# Talon_I2C.net
KiCad netlist of a schematic drawn in EAGLE
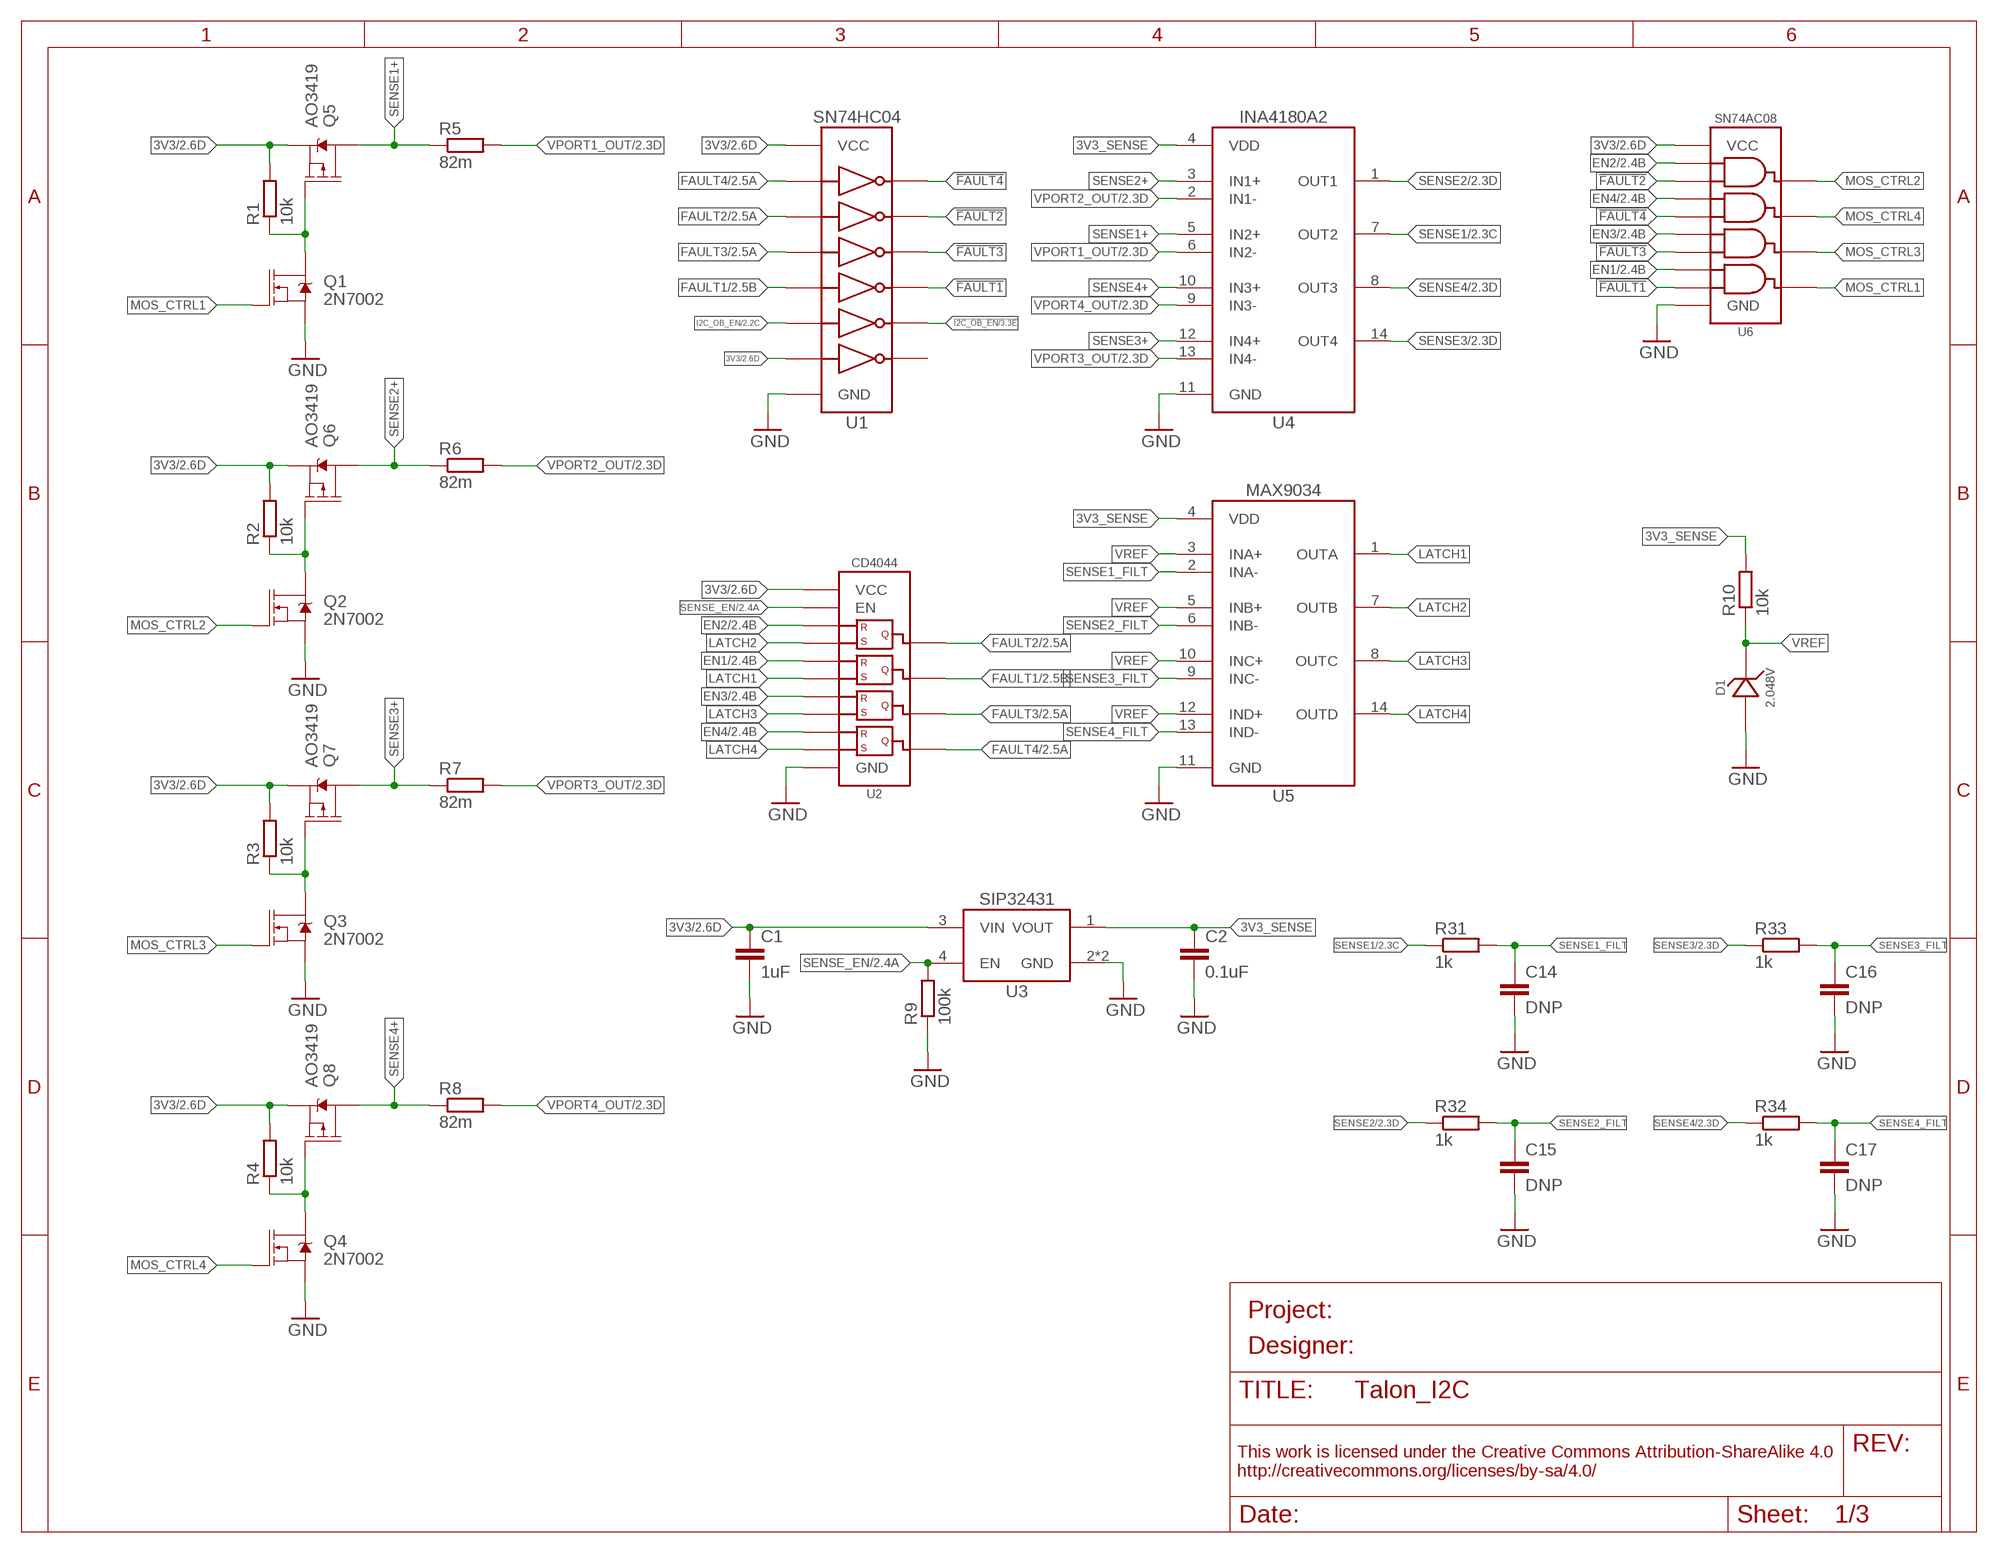
[diagram p0: schematic, sheet 1]
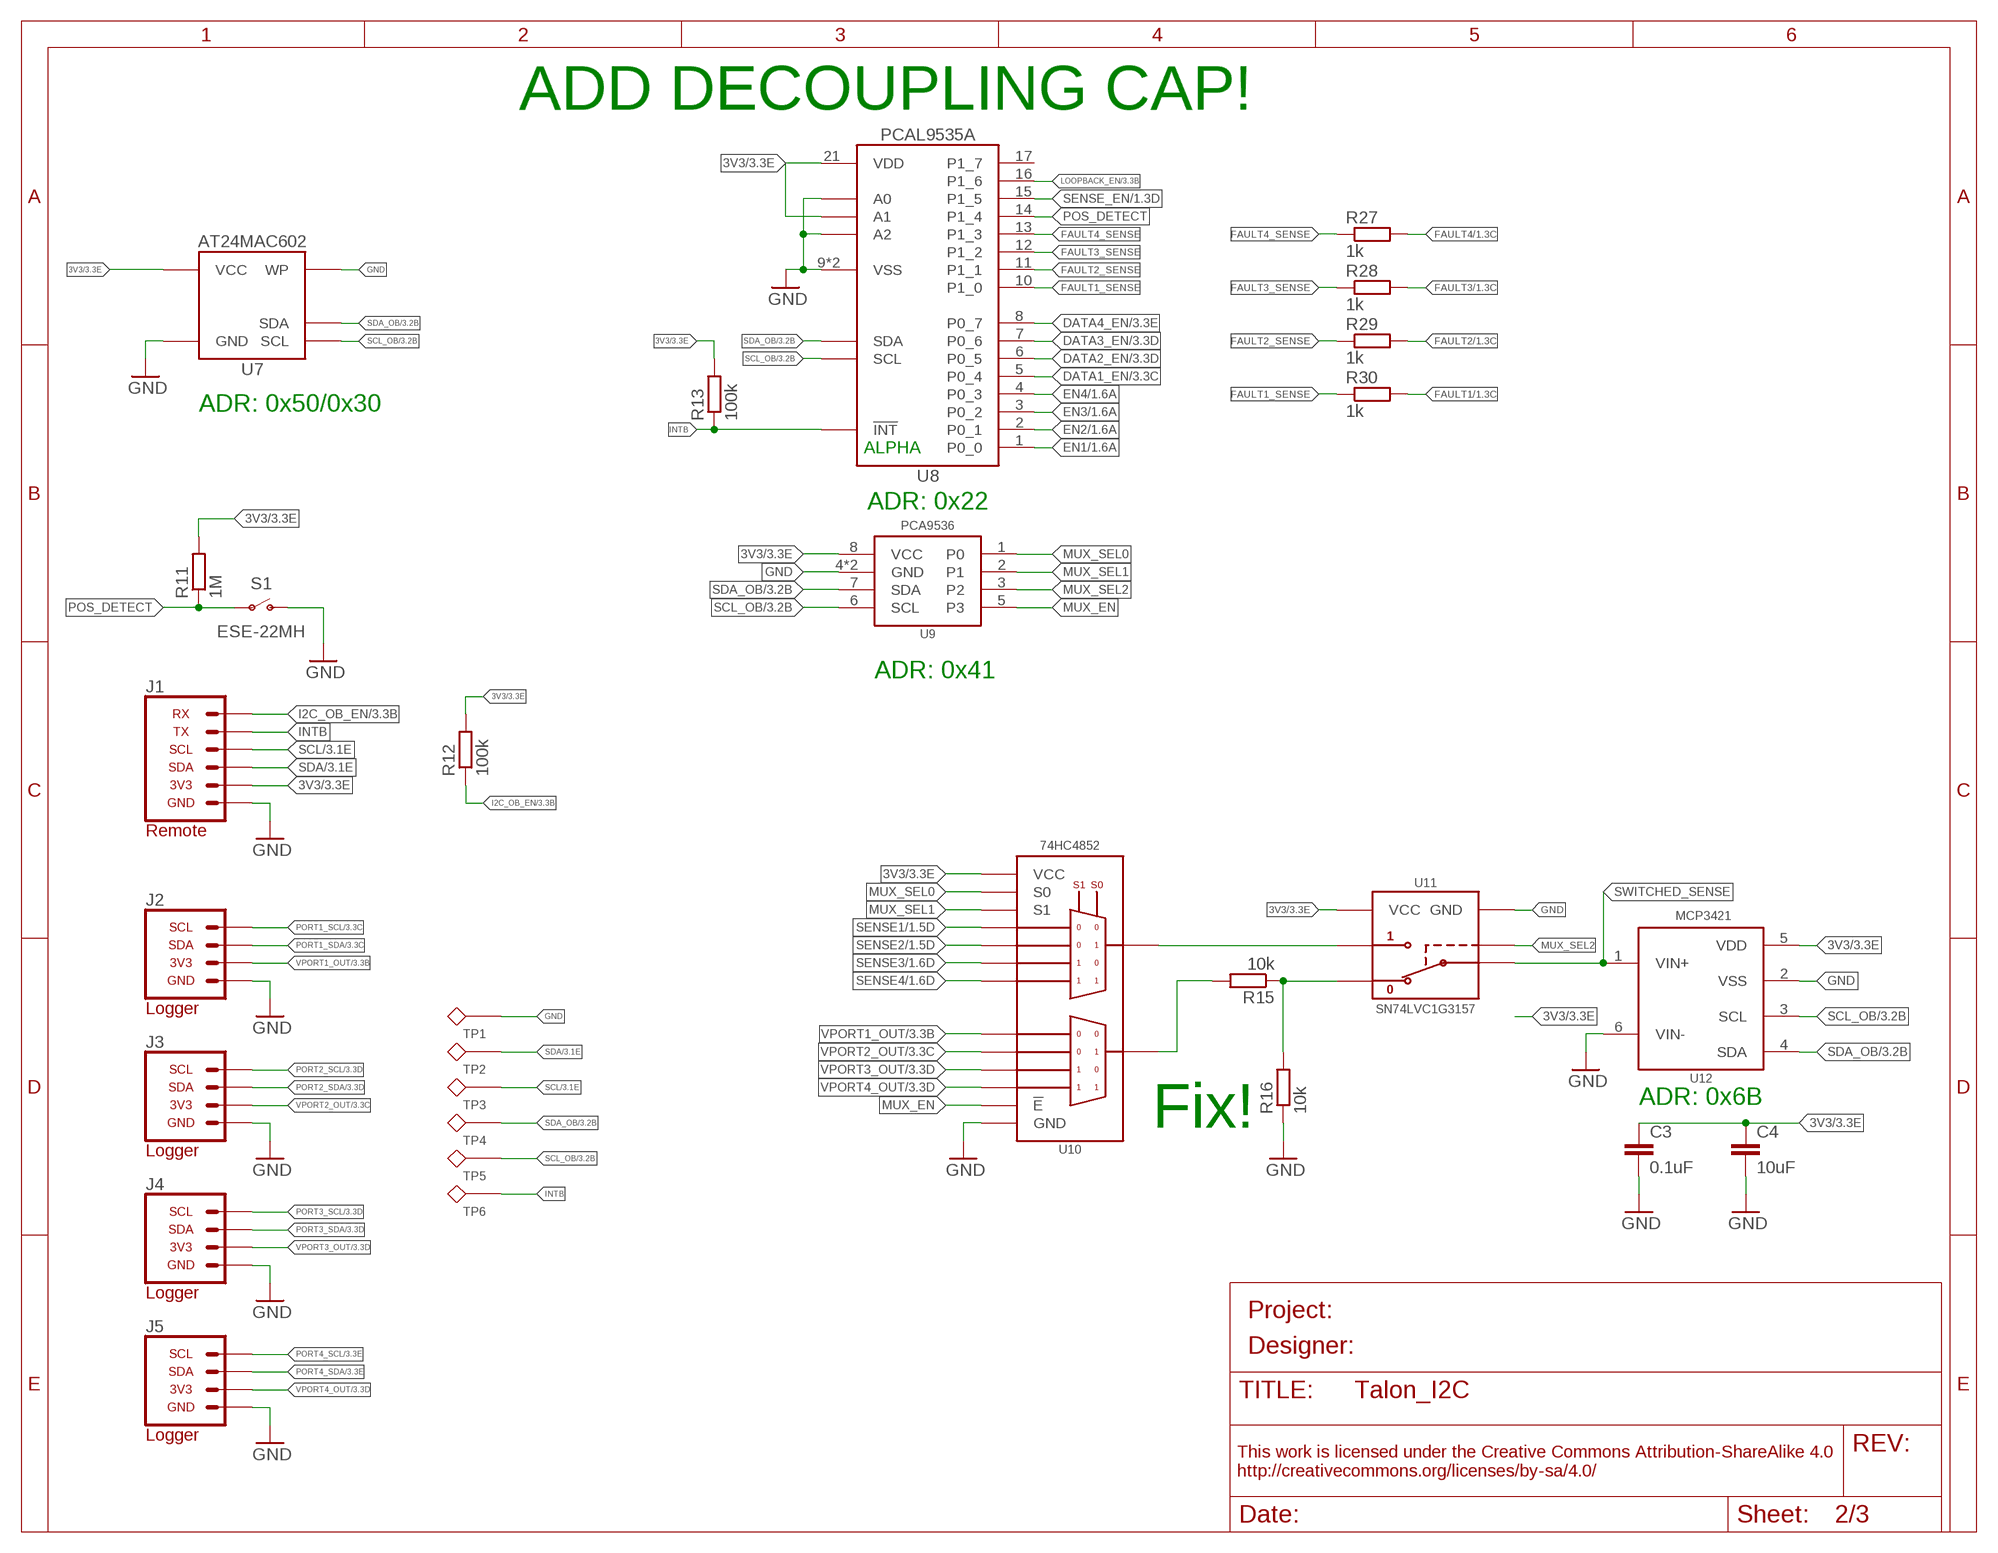
[diagram p1: schematic, sheet 2]
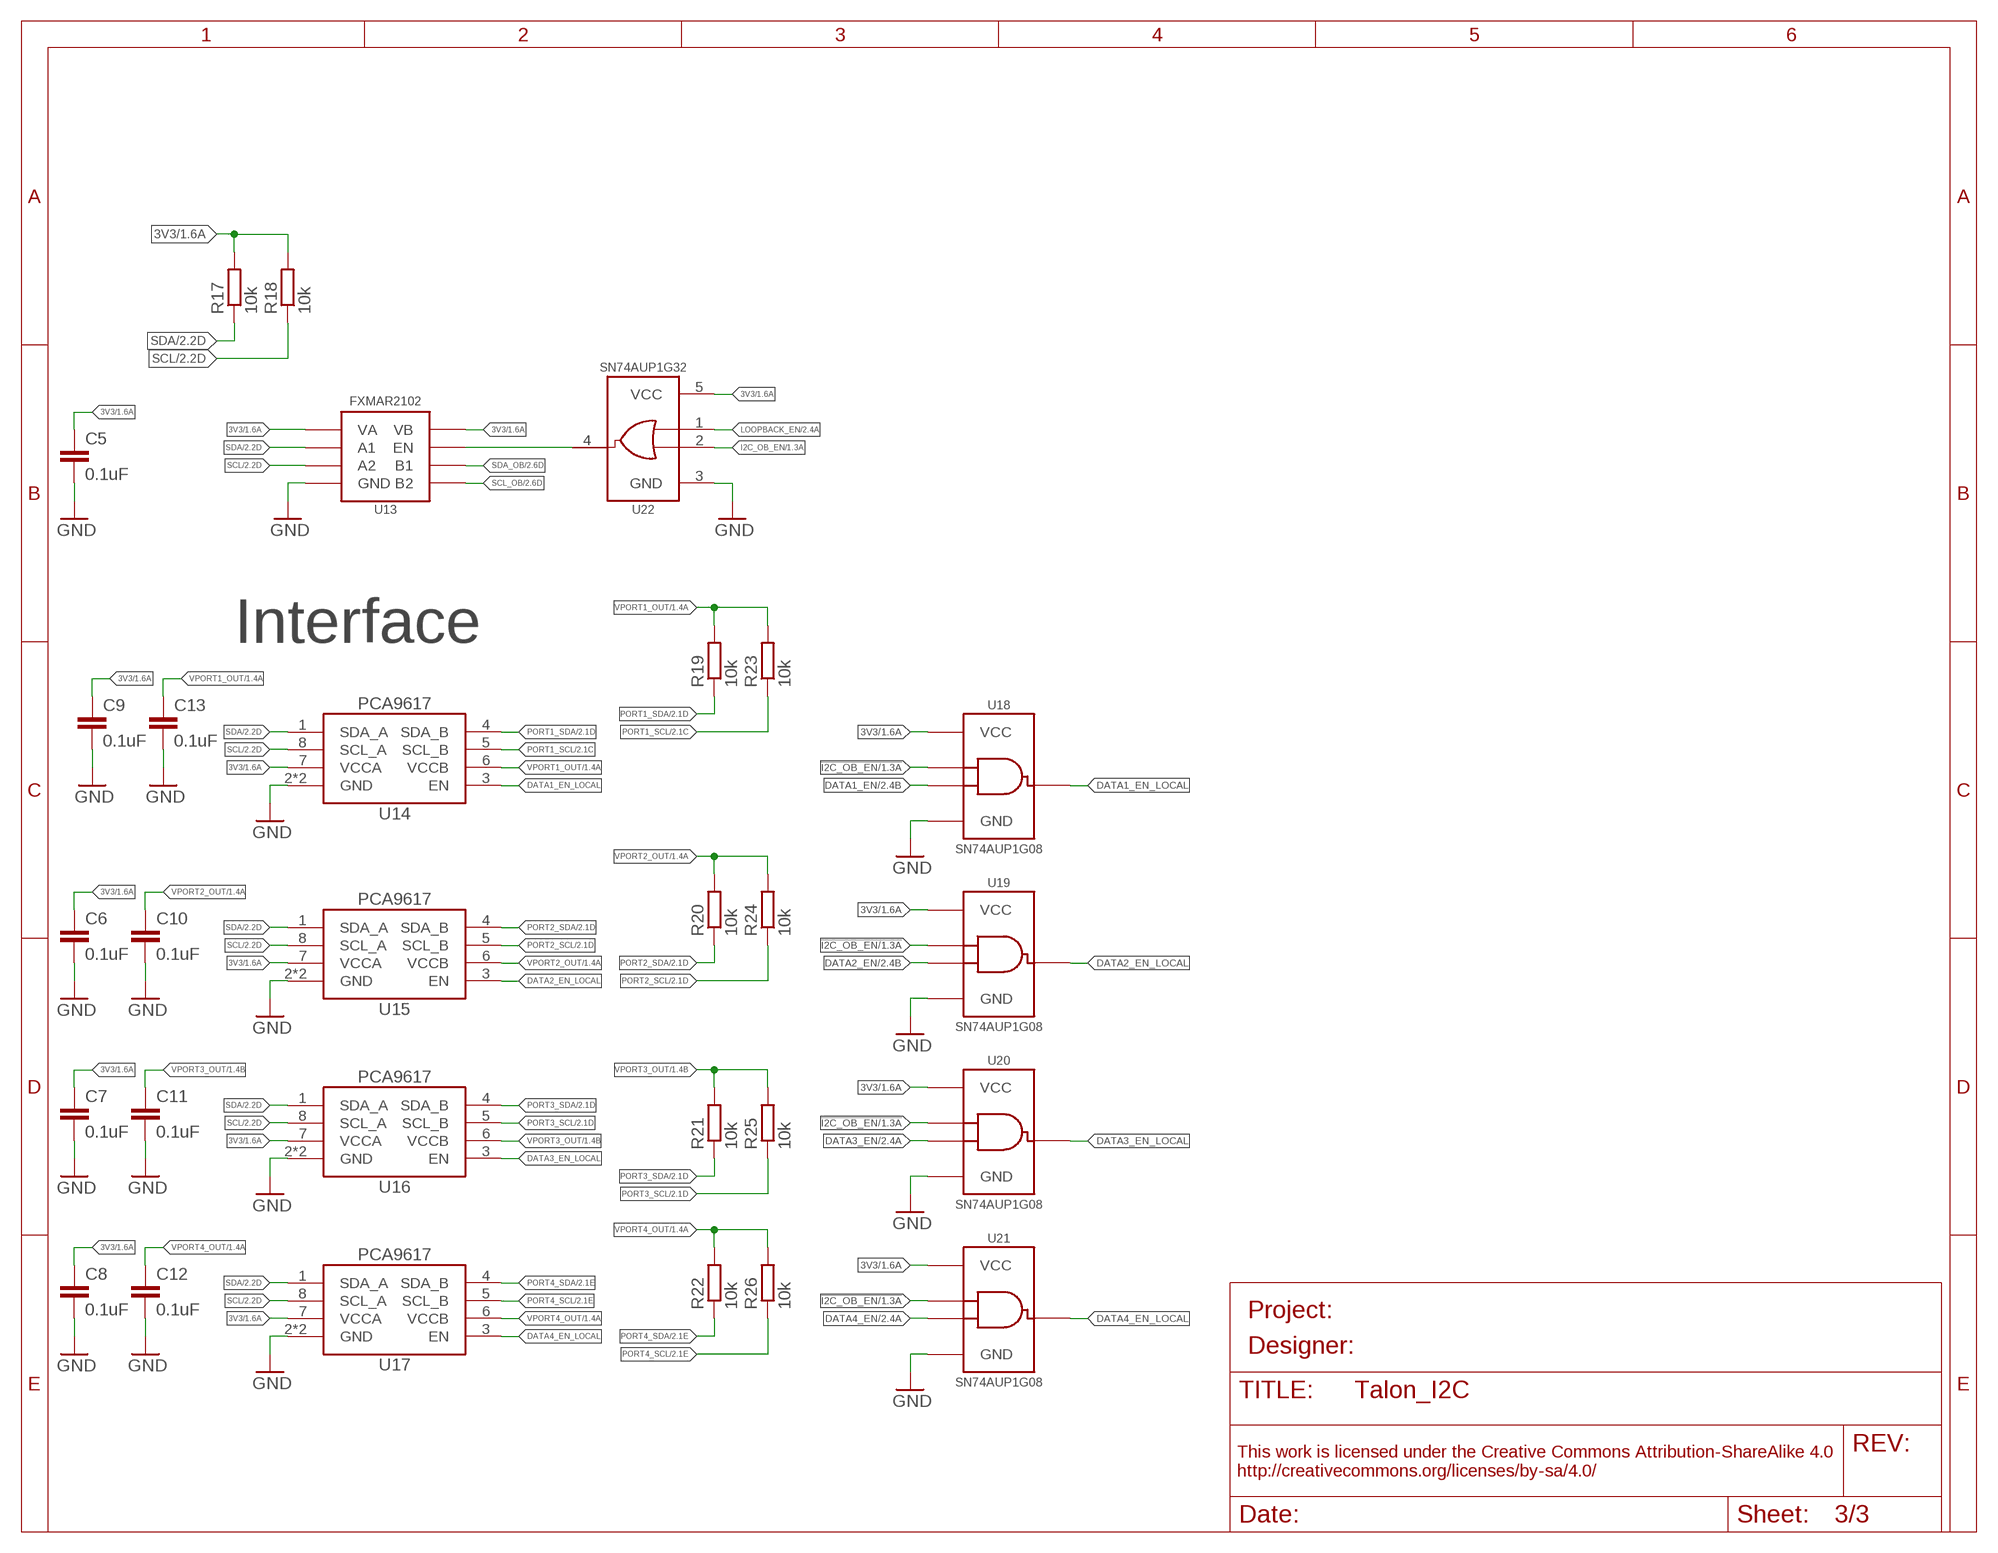
[diagram p2: schematic, sheet 3]

(export (version "E")
  (design (tool "Eeschema 10.0.6"))
  (components
    (comp (ref "C3")
      (value "0.1uF")
      (footprint "eagle-import:C0402")
      (fields (field (name "MF") "Murata") (field (name "MPN") "GCM155R71C104KA55D"))
      (libsource (lib "eagle-import") (part "C-EUC04020.1UF"))
    )
    (comp (ref "C4")
      (value "10uF")
      (footprint "eagle-import:C0805")
      (fields (field (name "MF") "Murata") (field (name "MPN") "GRM21BR61C106KE15K"))
      (libsource (lib "eagle-import") (part "C-EUC080510UF"))
    )
    (comp (ref "J1")
      (value "CONN_TALON_REMOTE")
      (footprint "eagle-import:1X06_MICROLOCKPLUS")
      (fields (field (name "DISP") "Remote") (field (name "MF") "Molex") (field (name "MPN") "2059570671"))
      (libsource (lib "eagle-import") (part "CONN_TALON_REMOTE"))
    )
    (comp (ref "J2")
      (value "CONN_I2C_LOGGER")
      (footprint "eagle-import:1X04_M8_TE_T404103_BOARDLOCK")
      (fields (field (name "DISP") "Logger") (field (name "MF") "TE") (field (name "MPN") "T4041037041-000"))
      (libsource (lib "eagle-import") (part "CONN_I2C_LOGGER"))
    )
    (comp (ref "J3")
      (value "CONN_I2C_LOGGER")
      (footprint "eagle-import:1X04_M8_TE_T404103_BOARDLOCK")
      (fields (field (name "DISP") "Logger") (field (name "MF") "TE") (field (name "MPN") "T4041037041-000"))
      (libsource (lib "eagle-import") (part "CONN_I2C_LOGGER"))
    )
    (comp (ref "J4")
      (value "CONN_I2C_LOGGER")
      (footprint "eagle-import:1X04_M8_TE_T404103_BOARDLOCK")
      (fields (field (name "DISP") "Logger") (field (name "MF") "TE") (field (name "MPN") "T4041037041-000"))
      (libsource (lib "eagle-import") (part "CONN_I2C_LOGGER"))
    )
    (comp (ref "J5")
      (value "CONN_I2C_LOGGER")
      (footprint "eagle-import:1X04_M8_TE_T404103_BOARDLOCK")
      (fields (field (name "DISP") "Logger") (field (name "MF") "TE") (field (name "MPN") "T4041037041-000"))
      (libsource (lib "eagle-import") (part "CONN_I2C_LOGGER"))
    )
    (comp (ref "R11")
      (value "1M")
      (footprint "eagle-import:R0402")
      (fields (field (name "MF") "Yageo") (field (name "MPN") "RC0402FR-071ML"))
      (libsource (lib "eagle-import") (part "R-EU_R04021M"))
    )
    (comp (ref "R12")
      (value "100k")
      (footprint "eagle-import:R0402")
      (fields (field (name "MF") "Yageo") (field (name "MPN") "RC0402FR-07100KL"))
      (libsource (lib "eagle-import") (part "R-EU_R0402100K"))
    )
    (comp (ref "R13")
      (value "100k")
      (footprint "eagle-import:R0402")
      (fields (field (name "MF") "Yageo") (field (name "MPN") "RC0402FR-07100KL"))
      (libsource (lib "eagle-import") (part "R-EU_R0402100K"))
    )
    (comp (ref "R15")
      (value "10k")
      (footprint "eagle-import:R0402")
      (fields (field (name "MF") "Yageo") (field (name "MPN") "RC0402FR-0710KL"))
      (libsource (lib "eagle-import") (part "R-EU_R040210K"))
    )
    (comp (ref "R16")
      (value "10k")
      (footprint "eagle-import:R0402")
      (fields (field (name "MF") "Yageo") (field (name "MPN") "RC0402FR-0710KL"))
      (libsource (lib "eagle-import") (part "R-EU_R040210K"))
    )
    (comp (ref "R27")
      (value "1k")
      (footprint "eagle-import:R0402")
      (fields (field (name "MF") "Yageo") (field (name "MPN") "RC0402FR-071KL"))
      (libsource (lib "eagle-import") (part "R-EU_R04021K"))
    )
    (comp (ref "R28")
      (value "1k")
      (footprint "eagle-import:R0402")
      (fields (field (name "MF") "Yageo") (field (name "MPN") "RC0402FR-071KL"))
      (libsource (lib "eagle-import") (part "R-EU_R04021K"))
    )
    (comp (ref "R29")
      (value "1k")
      (footprint "eagle-import:R0402")
      (fields (field (name "MF") "Yageo") (field (name "MPN") "RC0402FR-071KL"))
      (libsource (lib "eagle-import") (part "R-EU_R04021K"))
    )
    (comp (ref "R30")
      (value "1k")
      (footprint "eagle-import:R0402")
      (fields (field (name "MF") "Yageo") (field (name "MPN") "RC0402FR-071KL"))
      (libsource (lib "eagle-import") (part "R-EU_R04021K"))
    )
    (comp (ref "S1")
      (value "ESE-22MH")
      (footprint "eagle-import:ESE-22MH")
      (fields (field (name "MF") "Panasonic") (field (name "MPN") "ESE-22MH24"))
      (libsource (lib "eagle-import") (part "SPSTESE-22MH"))
    )
    (comp (ref "TP1")
      (value "TESTPOINTRCU")
      (footprint "eagle-import:TESTPOINT_0603")
      (fields (field (name "MF") "TE Connectivity") (field (name "MPN") "RCU-0C"))
      (libsource (lib "eagle-import") (part "TESTPOINTRCU"))
    )
    (comp (ref "TP2")
      (value "TESTPOINTRCU")
      (footprint "eagle-import:TESTPOINT_0603")
      (fields (field (name "MF") "TE Connectivity") (field (name "MPN") "RCU-0C"))
      (libsource (lib "eagle-import") (part "TESTPOINTRCU"))
    )
    (comp (ref "TP3")
      (value "TESTPOINTRCU")
      (footprint "eagle-import:TESTPOINT_0603")
      (fields (field (name "MF") "TE Connectivity") (field (name "MPN") "RCU-0C"))
      (libsource (lib "eagle-import") (part "TESTPOINTRCU"))
    )
    (comp (ref "TP4")
      (value "TESTPOINTRCU")
      (footprint "eagle-import:TESTPOINT_0603")
      (fields (field (name "MF") "TE Connectivity") (field (name "MPN") "RCU-0C"))
      (libsource (lib "eagle-import") (part "TESTPOINTRCU"))
    )
    (comp (ref "TP5")
      (value "TESTPOINTRCU")
      (footprint "eagle-import:TESTPOINT_0603")
      (fields (field (name "MF") "TE Connectivity") (field (name "MPN") "RCU-0C"))
      (libsource (lib "eagle-import") (part "TESTPOINTRCU"))
    )
    (comp (ref "TP6")
      (value "TESTPOINTRCU")
      (footprint "eagle-import:TESTPOINT_0603")
      (fields (field (name "MF") "TE Connectivity") (field (name "MPN") "RCU-0C"))
      (libsource (lib "eagle-import") (part "TESTPOINTRCU"))
    )
    (comp (ref "U7")
      (value "AT24MAC602SOT23")
      (footprint "eagle-import:SOT23-5")
      (fields
        (field (name "DISP") "AT24MAC602")
        (field (name "MF") "Microchip")
        (field (name "MPN") "AT24MAC602-STUM-T")
      )
      (libsource (lib "eagle-import") (part "AT24MAC02SOT236"))
    )
    (comp (ref "U8")
      (value "PCAL9535AQFN")
      (footprint "eagle-import:QFN24")
      (fields
        (field (name "DISP") "PCAL9535A")
        (field (name "MF") "NXP")
        (field (name "MPN") "PCAL9535AHF,128")
      )
      (libsource (lib "eagle-import") (part "PCAL955AQFN3"))
    )
    (comp (ref "U9")
      (value "PCA9536DFN")
      (footprint "eagle-import:DFN_8_3X3")
      (fields (field (name "MF") "NXP") (field (name "MPN") "PCA9536TK,118"))
      (libsource (lib "eagle-import") (part "PCA9536DFN"))
    )
    (comp (ref "U10")
      (value "74HC4852")
      (footprint "eagle-import:VQFN-16")
      (fields
        (field (name "DISP") "74HC4852")
        (field (name "MF") "Nexperia")
        (field (name "MPN") "74HC4852BQ-Q100,11")
      )
      (libsource (lib "eagle-import") (part "74HC4852"))
    )
    (comp (ref "U11")
      (value "SN74LVC1G3157SC70")
      (footprint "eagle-import:DCK_R-PDSO-G6")
      (fields
        (field (name "DISP") "SN74LVC1G3157")
        (field (name "MF") "TI")
        (field (name "MPN") "SN74LVC1G3157DCKR")
      )
      (libsource (lib "eagle-import") (part "SN74LVC1G3157SC70"))
    )
    (comp (ref "U12")
      (value "MCP3421A3")
      (footprint "eagle-import:SOT23-6L")
      (fields
        (field (name "DISP") "MCP3421")
        (field (name "MF") "Microchip")
        (field (name "MPN") "MCP3421A3T-E/CH")
      )
      (libsource (lib "eagle-import") (part "MCP3421A3"))
    )
    (comp (ref "C5")
      (value "0.1uF")
      (footprint "eagle-import:C0402")
      (fields (field (name "MF") "Murata") (field (name "MPN") "GCM155R71C104KA55D"))
      (libsource (lib "eagle-import") (part "C-EUC04020.1UF"))
    )
    (comp (ref "C6")
      (value "0.1uF")
      (footprint "eagle-import:C0402")
      (fields (field (name "MF") "Murata") (field (name "MPN") "GCM155R71C104KA55D"))
      (libsource (lib "eagle-import") (part "C-EUC04020.1UF"))
    )
    (comp (ref "C7")
      (value "0.1uF")
      (footprint "eagle-import:C0402")
      (fields (field (name "MF") "Murata") (field (name "MPN") "GCM155R71C104KA55D"))
      (libsource (lib "eagle-import") (part "C-EUC04020.1UF"))
    )
    (comp (ref "C8")
      (value "0.1uF")
      (footprint "eagle-import:C0402")
      (fields (field (name "MF") "Murata") (field (name "MPN") "GCM155R71C104KA55D"))
      (libsource (lib "eagle-import") (part "C-EUC04020.1UF"))
    )
    (comp (ref "C9")
      (value "0.1uF")
      (footprint "eagle-import:C0402")
      (fields (field (name "MF") "Murata") (field (name "MPN") "GCM155R71C104KA55D"))
      (libsource (lib "eagle-import") (part "C-EUC04020.1UF"))
    )
    (comp (ref "C10")
      (value "0.1uF")
      (footprint "eagle-import:C0402")
      (fields (field (name "MF") "Murata") (field (name "MPN") "GCM155R71C104KA55D"))
      (libsource (lib "eagle-import") (part "C-EUC04020.1UF"))
    )
    (comp (ref "C11")
      (value "0.1uF")
      (footprint "eagle-import:C0402")
      (fields (field (name "MF") "Murata") (field (name "MPN") "GCM155R71C104KA55D"))
      (libsource (lib "eagle-import") (part "C-EUC04020.1UF"))
    )
    (comp (ref "C12")
      (value "0.1uF")
      (footprint "eagle-import:C0402")
      (fields (field (name "MF") "Murata") (field (name "MPN") "GCM155R71C104KA55D"))
      (libsource (lib "eagle-import") (part "C-EUC04020.1UF"))
    )
    (comp (ref "C13")
      (value "0.1uF")
      (footprint "eagle-import:C0402")
      (fields (field (name "MF") "Murata") (field (name "MPN") "GCM155R71C104KA55D"))
      (libsource (lib "eagle-import") (part "C-EUC04020.1UF"))
    )
    (comp (ref "R17")
      (value "10k")
      (footprint "eagle-import:R0402")
      (fields (field (name "MF") "Yageo") (field (name "MPN") "RC0402FR-0710KL"))
      (libsource (lib "eagle-import") (part "R-EU_R040210K"))
    )
    (comp (ref "R18")
      (value "10k")
      (footprint "eagle-import:R0402")
      (fields (field (name "MF") "Yageo") (field (name "MPN") "RC0402FR-0710KL"))
      (libsource (lib "eagle-import") (part "R-EU_R040210K"))
    )
    (comp (ref "R19")
      (value "10k")
      (footprint "eagle-import:R0402")
      (fields (field (name "MF") "Yageo") (field (name "MPN") "RC0402FR-0710KL"))
      (libsource (lib "eagle-import") (part "R-EU_R040210K"))
    )
    (comp (ref "R20")
      (value "10k")
      (footprint "eagle-import:R0402")
      (fields (field (name "MF") "Yageo") (field (name "MPN") "RC0402FR-0710KL"))
      (libsource (lib "eagle-import") (part "R-EU_R040210K"))
    )
    (comp (ref "R21")
      (value "10k")
      (footprint "eagle-import:R0402")
      (fields (field (name "MF") "Yageo") (field (name "MPN") "RC0402FR-0710KL"))
      (libsource (lib "eagle-import") (part "R-EU_R040210K"))
    )
    (comp (ref "R22")
      (value "10k")
      (footprint "eagle-import:R0402")
      (fields (field (name "MF") "Yageo") (field (name "MPN") "RC0402FR-0710KL"))
      (libsource (lib "eagle-import") (part "R-EU_R040210K"))
    )
    (comp (ref "R23")
      (value "10k")
      (footprint "eagle-import:R0402")
      (fields (field (name "MF") "Yageo") (field (name "MPN") "RC0402FR-0710KL"))
      (libsource (lib "eagle-import") (part "R-EU_R040210K"))
    )
    (comp (ref "R24")
      (value "10k")
      (footprint "eagle-import:R0402")
      (fields (field (name "MF") "Yageo") (field (name "MPN") "RC0402FR-0710KL"))
      (libsource (lib "eagle-import") (part "R-EU_R040210K"))
    )
    (comp (ref "R25")
      (value "10k")
      (footprint "eagle-import:R0402")
      (fields (field (name "MF") "Yageo") (field (name "MPN") "RC0402FR-0710KL"))
      (libsource (lib "eagle-import") (part "R-EU_R040210K"))
    )
    (comp (ref "R26")
      (value "10k")
      (footprint "eagle-import:R0402")
      (fields (field (name "MF") "Yageo") (field (name "MPN") "RC0402FR-0710KL"))
      (libsource (lib "eagle-import") (part "R-EU_R040210K"))
    )
    (comp (ref "U13")
      (value "FXMAR2102UMLP")
      (footprint "eagle-import:UQFN-8_1.4X1.2")
      (fields
        (field (name "DISP") "FXMAR2102")
        (field (name "MF") "OnSemi")
        (field (name "MPN") "FXMAR2102UMX-F106")
      )
      (libsource (lib "eagle-import") (part "FXMAR2102UMLP"))
    )
    (comp (ref "U14")
      (value "PCA9617WSON")
      (footprint "eagle-import:WSON-8_2X3")
      (fields (field (name "MF") "NXP") (field (name "MPN") "PCA9617ATPZ"))
      (libsource (lib "eagle-import") (part "PCA9617WSON"))
    )
    (comp (ref "U15")
      (value "PCA9617WSON")
      (footprint "eagle-import:WSON-8_2X3")
      (fields (field (name "MF") "NXP") (field (name "MPN") "PCA9617ATPZ"))
      (libsource (lib "eagle-import") (part "PCA9617WSON"))
    )
    (comp (ref "U16")
      (value "PCA9617WSON")
      (footprint "eagle-import:WSON-8_2X3")
      (fields (field (name "MF") "NXP") (field (name "MPN") "PCA9617ATPZ"))
      (libsource (lib "eagle-import") (part "PCA9617WSON"))
    )
    (comp (ref "U17")
      (value "PCA9617WSON")
      (footprint "eagle-import:WSON-8_2X3")
      (fields (field (name "MF") "NXP") (field (name "MPN") "PCA9617ATPZ"))
      (libsource (lib "eagle-import") (part "PCA9617WSON"))
    )
    (comp (ref "U18")
      (value "SN74AUP1G08DCK")
      (footprint "eagle-import:DCK_R-PDSO-G5")
      (fields (field (name "MF") "TI") (field (name "MPN") "SN74AUP1G08DCKR"))
      (libsource (lib "eagle-import") (part "SN74AUP1G08DCK"))
    )
    (comp (ref "U19")
      (value "SN74AUP1G08DCK")
      (footprint "eagle-import:DCK_R-PDSO-G5")
      (fields (field (name "MF") "TI") (field (name "MPN") "SN74AUP1G08DCKR"))
      (libsource (lib "eagle-import") (part "SN74AUP1G08DCK"))
    )
    (comp (ref "U20")
      (value "SN74AUP1G08DCK")
      (footprint "eagle-import:DCK_R-PDSO-G5")
      (fields (field (name "MF") "TI") (field (name "MPN") "SN74AUP1G08DCKR"))
      (libsource (lib "eagle-import") (part "SN74AUP1G08DCK"))
    )
    (comp (ref "U21")
      (value "SN74AUP1G08DCK")
      (footprint "eagle-import:DCK_R-PDSO-G5")
      (fields (field (name "MF") "TI") (field (name "MPN") "SN74AUP1G08DCKR"))
      (libsource (lib "eagle-import") (part "SN74AUP1G08DCK"))
    )
    (comp (ref "U22")
      (value "SN74AUP1G32DCK")
      (footprint "eagle-import:DCK_R-PDSO-G5")
      (fields
        (field (name "DISP") "SN74AUP1G32")
        (field (name "MF") "TI")
        (field (name "MPN") "SN74AUP1G32DCKR")
      )
      (libsource (lib "eagle-import") (part "SN741G32DCKAUP"))
    )
    (comp (ref "C1")
      (value "1uF")
      (footprint "eagle-import:C0603")
      (fields (field (name "MF") "Yaiyo Yuden") (field (name "MPN") "EMK107BJ105KA-T"))
      (libsource (lib "eagle-import") (part "C-EUC06031UF"))
    )
    (comp (ref "C2")
      (value "0.1uF")
      (footprint "eagle-import:C0402")
      (fields (field (name "MF") "Murata") (field (name "MPN") "GCM155R71C104KA55D"))
      (libsource (lib "eagle-import") (part "C-EUC04020.1UF"))
    )
    (comp (ref "C14")
      (value "DNP")
      (footprint "eagle-import:C0402")
      (fields
        (field (name "MF") "Murata")
        (field (name "MPN") "GCM155R71C104KA55D")
        (field (name "DIGIKEY") "DNP")
        (field (name "MF_1") "N/A")
        (field (name "MPN_1") "DNP")
      )
      (libsource (lib "eagle-import") (part "C-EUC04020.1UF"))
    )
    (comp (ref "C15")
      (value "DNP")
      (footprint "eagle-import:C0402")
      (fields
        (field (name "MF") "Murata")
        (field (name "MPN") "GCM155R71C104KA55D")
        (field (name "DIGIKEY") "DNP")
        (field (name "MF_1") "N/A")
        (field (name "MPN_1") "DNP")
      )
      (libsource (lib "eagle-import") (part "C-EUC04020.1UF"))
    )
    (comp (ref "C16")
      (value "DNP")
      (footprint "eagle-import:C0402")
      (fields
        (field (name "MF") "Murata")
        (field (name "MPN") "GCM155R71C104KA55D")
        (field (name "DIGIKEY") "DNP")
        (field (name "MF_1") "N/A")
        (field (name "MPN_1") "DNP")
      )
      (libsource (lib "eagle-import") (part "C-EUC04020.1UF"))
    )
    (comp (ref "C17")
      (value "DNP")
      (footprint "eagle-import:C0402")
      (fields
        (field (name "MF") "Murata")
        (field (name "MPN") "GCM155R71C104KA55D")
        (field (name "DIGIKEY") "DNP")
        (field (name "MF_1") "N/A")
        (field (name "MPN_1") "DNP")
      )
      (libsource (lib "eagle-import") (part "C-EUC04020.1UF"))
    )
    (comp (ref "D1")
      (value "2.048V")
      (footprint "eagle-import:SOT23-3")
      (fields (field (name "MF") "TI") (field (name "MPN") "LM4040CIM3-2.0/NOPB"))
      (libsource (lib "eagle-import") (part "LM40402.048"))
    )
    (comp (ref "Q1")
      (value "2N7002")
      (footprint "eagle-import:SOT23-3")
      (fields (field (name "MF") "Nexperia") (field (name "MPN") "2N7002P,215"))
      (libsource (lib "eagle-import") (part "MOSFET-NCH-2N7002P"))
    )
    (comp (ref "Q2")
      (value "2N7002")
      (footprint "eagle-import:SOT23-3")
      (fields (field (name "MF") "Nexperia") (field (name "MPN") "2N7002P,215"))
      (libsource (lib "eagle-import") (part "MOSFET-NCH-2N7002P"))
    )
    (comp (ref "Q3")
      (value "2N7002")
      (footprint "eagle-import:SOT23-3")
      (fields (field (name "MF") "Nexperia") (field (name "MPN") "2N7002P,215"))
      (libsource (lib "eagle-import") (part "MOSFET-NCH-2N7002P"))
    )
    (comp (ref "Q4")
      (value "2N7002")
      (footprint "eagle-import:SOT23-3")
      (fields (field (name "MF") "Nexperia") (field (name "MPN") "2N7002P,215"))
      (libsource (lib "eagle-import") (part "MOSFET-NCH-2N7002P"))
    )
    (comp (ref "Q5")
      (value "AO3419")
      (footprint "eagle-import:SOT23-3")
      (fields (field (name "MF") "Alpha and Omega"))
      (libsource (lib "eagle-import") (part "MOSFET-PCH-AO3419"))
    )
    (comp (ref "Q6")
      (value "AO3419")
      (footprint "eagle-import:SOT23-3")
      (fields (field (name "MF") "Alpha and Omega"))
      (libsource (lib "eagle-import") (part "MOSFET-PCH-AO3419"))
    )
    (comp (ref "Q7")
      (value "AO3419")
      (footprint "eagle-import:SOT23-3")
      (fields (field (name "MF") "Alpha and Omega"))
      (libsource (lib "eagle-import") (part "MOSFET-PCH-AO3419"))
    )
    (comp (ref "Q8")
      (value "AO3419")
      (footprint "eagle-import:SOT23-3")
      (fields (field (name "MF") "Alpha and Omega"))
      (libsource (lib "eagle-import") (part "MOSFET-PCH-AO3419"))
    )
    (comp (ref "R1")
      (value "10k")
      (footprint "eagle-import:R0402")
      (fields (field (name "MF") "Yageo") (field (name "MPN") "RC0402FR-0710KL"))
      (libsource (lib "eagle-import") (part "R-EU_R040210K"))
    )
    (comp (ref "R2")
      (value "10k")
      (footprint "eagle-import:R0402")
      (fields (field (name "MF") "Yageo") (field (name "MPN") "RC0402FR-0710KL"))
      (libsource (lib "eagle-import") (part "R-EU_R040210K"))
    )
    (comp (ref "R3")
      (value "10k")
      (footprint "eagle-import:R0402")
      (fields (field (name "MF") "Yageo") (field (name "MPN") "RC0402FR-0710KL"))
      (libsource (lib "eagle-import") (part "R-EU_R040210K"))
    )
    (comp (ref "R4")
      (value "10k")
      (footprint "eagle-import:R0402")
      (fields (field (name "MF") "Yageo") (field (name "MPN") "RC0402FR-0710KL"))
      (libsource (lib "eagle-import") (part "R-EU_R040210K"))
    )
    (comp (ref "R5")
      (value "82m")
      (footprint "eagle-import:R0603")
      (fields (field (name "MF") "Susumu") (field (name "MPN") "RL0816T-R082-F"))
      (libsource (lib "eagle-import") (part "R-EU_R06030.082"))
    )
    (comp (ref "R6")
      (value "82m")
      (footprint "eagle-import:R0603")
      (fields (field (name "MF") "Susumu") (field (name "MPN") "RL0816T-R082-F"))
      (libsource (lib "eagle-import") (part "R-EU_R06030.082"))
    )
    (comp (ref "R7")
      (value "82m")
      (footprint "eagle-import:R0603")
      (fields (field (name "MF") "Susumu") (field (name "MPN") "RL0816T-R082-F"))
      (libsource (lib "eagle-import") (part "R-EU_R06030.082"))
    )
    (comp (ref "R8")
      (value "82m")
      (footprint "eagle-import:R0603")
      (fields (field (name "MF") "Susumu") (field (name "MPN") "RL0816T-R082-F"))
      (libsource (lib "eagle-import") (part "R-EU_R06030.082"))
    )
    (comp (ref "R9")
      (value "100k")
      (footprint "eagle-import:R0402")
      (fields (field (name "MF") "Yageo") (field (name "MPN") "RC0402FR-07100KL"))
      (libsource (lib "eagle-import") (part "R-EU_R0402100K"))
    )
    (comp (ref "R10")
      (value "10k")
      (footprint "eagle-import:R0402")
      (fields (field (name "MF") "Yageo") (field (name "MPN") "RC0402FR-0710KL"))
      (libsource (lib "eagle-import") (part "R-EU_R040210K"))
    )
    (comp (ref "R31")
      (value "1k")
      (footprint "eagle-import:R0402")
      (fields (field (name "MF") "Yageo") (field (name "MPN") "RC0402FR-071KL"))
      (libsource (lib "eagle-import") (part "R-EU_R04021K"))
    )
    (comp (ref "R32")
      (value "1k")
      (footprint "eagle-import:R0402")
      (fields (field (name "MF") "Yageo") (field (name "MPN") "RC0402FR-071KL"))
      (libsource (lib "eagle-import") (part "R-EU_R04021K"))
    )
    (comp (ref "R33")
      (value "1k")
      (footprint "eagle-import:R0402")
      (fields (field (name "MF") "Yageo") (field (name "MPN") "RC0402FR-071KL"))
      (libsource (lib "eagle-import") (part "R-EU_R04021K"))
    )
    (comp (ref "R34")
      (value "1k")
      (footprint "eagle-import:R0402")
      (fields (field (name "MF") "Yageo") (field (name "MPN") "RC0402FR-071KL"))
      (libsource (lib "eagle-import") (part "R-EU_R04021K"))
    )
    (comp (ref "U1")
      (value "SN74HC04")
      (footprint "eagle-import:TSSOP14")
      (fields (field (name "MF") "TI") (field (name "MPN") "SN74HC04PWR"))
      (libsource (lib "eagle-import") (part "SN74HC04"))
    )
    (comp (ref "U2")
      (value "CD4044")
      (footprint "eagle-import:TSSOP16")
      (fields (field (name "DISP") "CD4044") (field (name "MF") "TI") (field (name "MPN") "CD4044BPWR"))
      (libsource (lib "eagle-import") (part "CD4044"))
    )
    (comp (ref "U3")
      (value "SIP32431TDFN")
      (footprint "eagle-import:TDFN_4")
      (fields
        (field (name "DISP") "SIP32431")
        (field (name "MF") "Vishay")
        (field (name "MPN") "SIP32431DNP3-T1GE4")
      )
      (libsource (lib "eagle-import") (part "SIP3243TDFN1"))
    )
    (comp (ref "U4")
      (value "INA4180A2")
      (footprint "eagle-import:TSSOP14")
      (fields (field (name "DISP") "INA4180A2") (field (name "MF") "TI") (field (name "MPN") "INA4180A2IPWR"))
      (libsource (lib "eagle-import") (part "INA4180A2"))
    )
    (comp (ref "U5")
      (value "MAX9034TSSOP")
      (footprint "eagle-import:TSSOP14")
      (fields (field (name "DISP") "MAX9034") (field (name "MF") "Maxim") (field (name "MPN") "MAX9034AUD+T"))
      (libsource (lib "eagle-import") (part "MAX9034TSSOP"))
    )
    (comp (ref "U6")
      (value "SN74AC08")
      (footprint "eagle-import:TSSOP14")
      (fields (field (name "MF") "TI") (field (name "MPN") "SN74AC08PWR"))
      (libsource (lib "eagle-import") (part "SN74AC08"))
    )
  )
  (nets
    (net (code "1") (name "3V3") (class "Default")
      (node (ref "C1") (pin "1") (pinfunction "1_1") (pintype "passive"))
      (node (ref "C3") (pin "1") (pinfunction "1_1") (pintype "passive"))
      (node (ref "C4") (pin "1") (pinfunction "1_1") (pintype "passive"))
      (node (ref "C5") (pin "1") (pinfunction "1_1") (pintype "passive"))
      (node (ref "C6") (pin "1") (pinfunction "1_1") (pintype "passive"))
      (node (ref "C7") (pin "1") (pinfunction "1_1") (pintype "passive"))
      (node (ref "C8") (pin "1") (pinfunction "1_1") (pintype "passive"))
      (node (ref "C9") (pin "1") (pinfunction "1_1") (pintype "passive"))
      (node (ref "J1") (pin "2") (pinfunction "3V3_2") (pintype "passive"))
      (node (ref "Q5") (pin "2") (pinfunction "S_2") (pintype "bidirectional"))
      (node (ref "Q6") (pin "2") (pinfunction "S_2") (pintype "bidirectional"))
      (node (ref "Q7") (pin "2") (pinfunction "S_2") (pintype "bidirectional"))
      (node (ref "Q8") (pin "2") (pinfunction "S_2") (pintype "bidirectional"))
      (node (ref "R1") (pin "2") (pinfunction "2_2") (pintype "passive"))
      (node (ref "R11") (pin "2") (pinfunction "2_2") (pintype "passive"))
      (node (ref "R12") (pin "2") (pinfunction "2_2") (pintype "passive"))
      (node (ref "R13") (pin "2") (pinfunction "2_2") (pintype "passive"))
      (node (ref "R17") (pin "2") (pinfunction "2_2") (pintype "passive"))
      (node (ref "R18") (pin "2") (pinfunction "2_2") (pintype "passive"))
      (node (ref "R2") (pin "2") (pinfunction "2_2") (pintype "passive"))
      (node (ref "R3") (pin "2") (pinfunction "2_2") (pintype "passive"))
      (node (ref "R4") (pin "2") (pinfunction "2_2") (pintype "passive"))
      (node (ref "U1") (pin "13") (pinfunction "A6_13") (pintype "input"))
      (node (ref "U1") (pin "14") (pinfunction "VCC_14") (pintype "power_in"))
      (node (ref "U10") (pin "16") (pinfunction "VCC_16") (pintype "power_in"))
      (node (ref "U11") (pin "5") (pinfunction "VCC_5") (pintype "power_in"))
      (node (ref "U12") (pin "5") (pinfunction "VDD_5") (pintype "passive"))
      (node (ref "U13") (pin "1") (pinfunction "VA_1") (pintype "power_in"))
      (node (ref "U13") (pin "8") (pinfunction "VB_8") (pintype "power_in"))
      (node (ref "U14") (pin "7") (pinfunction "VCCA_7") (pintype "power_in"))
      (node (ref "U15") (pin "7") (pinfunction "VCCA_7") (pintype "power_in"))
      (node (ref "U16") (pin "7") (pinfunction "VCCA_7") (pintype "power_in"))
      (node (ref "U17") (pin "7") (pinfunction "VCCA_7") (pintype "power_in"))
      (node (ref "U18") (pin "5") (pinfunction "VCC_5") (pintype "power_in"))
      (node (ref "U19") (pin "5") (pinfunction "VCC_5") (pintype "power_in"))
      (node (ref "U2") (pin "16") (pinfunction "VCC_16") (pintype "power_in"))
      (node (ref "U20") (pin "5") (pinfunction "VCC_5") (pintype "power_in"))
      (node (ref "U21") (pin "5") (pinfunction "VCC_5") (pintype "power_in"))
      (node (ref "U22") (pin "5") (pinfunction "VCC_5") (pintype "power_in"))
      (node (ref "U3") (pin "3") (pinfunction "VIN_3") (pintype "power_in"))
      (node (ref "U6") (pin "14") (pinfunction "VCC_14") (pintype "power_in"))
      (node (ref "U7") (pin "4") (pinfunction "VCC_4") (pintype "power_in"))
      (node (ref "U8") (pin "21") (pinfunction "VDD_21") (pintype "power_in"))
      (node (ref "U8") (pin "23") (pinfunction "A1_23") (pintype "input"))
      (node (ref "U9") (pin "8") (pinfunction "VCC_8") (pintype "power_in"))
    )
    (net (code "2") (name "3V3_SENSE") (class "Default")
      (node (ref "C2") (pin "1") (pinfunction "1_1") (pintype "passive"))
      (node (ref "R10") (pin "2") (pinfunction "2_2") (pintype "passive"))
      (node (ref "U3") (pin "1") (pinfunction "VOUT_1") (pintype "power_in"))
      (node (ref "U4") (pin "4") (pinfunction "VDD_4") (pintype "power_in"))
      (node (ref "U5") (pin "4") (pinfunction "VDD_4") (pintype "power_in"))
    )
    (net (code "3") (name "DATA1_EN") (class "Default")
      (node (ref "U18") (pin "2") (pinfunction "B_2") (pintype "input"))
      (node (ref "U8") (pin "5") (pinfunction "P0_4_5") (pintype "bidirectional"))
    )
    (net (code "4") (name "DATA1_EN_LOCAL") (class "Default")
      (node (ref "U14") (pin "3") (pinfunction "EN_3") (pintype "open_collector"))
      (node (ref "U18") (pin "4") (pinfunction "Y_4") (pintype "output"))
    )
    (net (code "5") (name "DATA2_EN") (class "Default")
      (node (ref "U19") (pin "2") (pinfunction "B_2") (pintype "input"))
      (node (ref "U8") (pin "6") (pinfunction "P0_5_6") (pintype "bidirectional"))
    )
    (net (code "6") (name "DATA2_EN_LOCAL") (class "Default")
      (node (ref "U15") (pin "3") (pinfunction "EN_3") (pintype "open_collector"))
      (node (ref "U19") (pin "4") (pinfunction "Y_4") (pintype "output"))
    )
    (net (code "7") (name "DATA3_EN") (class "Default")
      (node (ref "U20") (pin "2") (pinfunction "B_2") (pintype "input"))
      (node (ref "U8") (pin "7") (pinfunction "P0_6_7") (pintype "bidirectional"))
    )
    (net (code "8") (name "DATA3_EN_LOCAL") (class "Default")
      (node (ref "U16") (pin "3") (pinfunction "EN_3") (pintype "open_collector"))
      (node (ref "U20") (pin "4") (pinfunction "Y_4") (pintype "output"))
    )
    (net (code "9") (name "DATA4_EN") (class "Default")
      (node (ref "U21") (pin "2") (pinfunction "B_2") (pintype "input"))
      (node (ref "U8") (pin "8") (pinfunction "P0_7_8") (pintype "bidirectional"))
    )
    (net (code "10") (name "DATA4_EN_LOCAL") (class "Default")
      (node (ref "U17") (pin "3") (pinfunction "EN_3") (pintype "open_collector"))
      (node (ref "U21") (pin "4") (pinfunction "Y_4") (pintype "output"))
    )
    (net (code "11") (name "EN1") (class "Default")
      (node (ref "U2") (pin "6") (pinfunction "R2_6") (pintype "input"))
      (node (ref "U6") (pin "12") (pinfunction "A4_12") (pintype "input"))
      (node (ref "U8") (pin "1") (pinfunction "P0_0_1") (pintype "bidirectional"))
    )
    (net (code "12") (name "EN2") (class "Default")
      (node (ref "U2") (pin "4") (pinfunction "R1_4") (pintype "input"))
      (node (ref "U6") (pin "1") (pinfunction "A1_1") (pintype "input"))
      (node (ref "U8") (pin "2") (pinfunction "P0_1_2") (pintype "bidirectional"))
    )
    (net (code "13") (name "EN3") (class "Default")
      (node (ref "U2") (pin "12") (pinfunction "R3_12") (pintype "input"))
      (node (ref "U6") (pin "9") (pinfunction "A3_9") (pintype "input"))
      (node (ref "U8") (pin "3") (pinfunction "P0_2_3") (pintype "bidirectional"))
    )
    (net (code "14") (name "EN4") (class "Default")
      (node (ref "U2") (pin "14") (pinfunction "R4_14") (pintype "input"))
      (node (ref "U6") (pin "4") (pinfunction "A2_4") (pintype "input"))
      (node (ref "U8") (pin "4") (pinfunction "P0_3_4") (pintype "bidirectional"))
    )
    (net (code "15") (name "FAULT1") (class "Default")
      (node (ref "R30") (pin "2") (pinfunction "2_2") (pintype "passive"))
      (node (ref "U1") (pin "9") (pinfunction "A4_9") (pintype "input"))
      (node (ref "U2") (pin "9") (pinfunction "Q2_9") (pintype "output"))
    )
    (net (code "16") (name "FAULT1_SENSE") (class "Default")
      (node (ref "R30") (pin "1") (pinfunction "1_1") (pintype "passive"))
      (node (ref "U8") (pin "10") (pinfunction "P1_0_10") (pintype "bidirectional"))
    )
    (net (code "17") (name "FAULT2") (class "Default")
      (node (ref "R29") (pin "2") (pinfunction "2_2") (pintype "passive"))
      (node (ref "U1") (pin "3") (pinfunction "A2_3") (pintype "input"))
      (node (ref "U2") (pin "13") (pinfunction "Q1_13") (pintype "output"))
    )
    (net (code "18") (name "FAULT2_SENSE") (class "Default")
      (node (ref "R29") (pin "1") (pinfunction "1_1") (pintype "passive"))
      (node (ref "U8") (pin "11") (pinfunction "P1_1_11") (pintype "bidirectional"))
    )
    (net (code "19") (name "FAULT3") (class "Default")
      (node (ref "R28") (pin "2") (pinfunction "2_2") (pintype "passive"))
      (node (ref "U1") (pin "5") (pinfunction "A3_5") (pintype "input"))
      (node (ref "U2") (pin "10") (pinfunction "Q3_10") (pintype "output"))
    )
    (net (code "20") (name "FAULT3_SENSE") (class "Default")
      (node (ref "R28") (pin "1") (pinfunction "1_1") (pintype "passive"))
      (node (ref "U8") (pin "12") (pinfunction "P1_2_12") (pintype "bidirectional"))
    )
    (net (code "21") (name "FAULT4") (class "Default")
      (node (ref "R27") (pin "2") (pinfunction "2_2") (pintype "passive"))
      (node (ref "U1") (pin "1") (pinfunction "A1_1") (pintype "input"))
      (node (ref "U2") (pin "1") (pinfunction "Q4_1") (pintype "output"))
    )
    (net (code "22") (name "FAULT4_SENSE") (class "Default")
      (node (ref "R27") (pin "1") (pinfunction "1_1") (pintype "passive"))
      (node (ref "U8") (pin "13") (pinfunction "P1_3_13") (pintype "bidirectional"))
    )
    (net (code "23") (name "GND") (class "Default")
      (node (ref "C1") (pin "2") (pinfunction "2_2") (pintype "passive"))
      (node (ref "C10") (pin "2") (pinfunction "2_2") (pintype "passive"))
      (node (ref "C11") (pin "2") (pinfunction "2_2") (pintype "passive"))
      (node (ref "C12") (pin "2") (pinfunction "2_2") (pintype "passive"))
      (node (ref "C13") (pin "2") (pinfunction "2_2") (pintype "passive"))
      (node (ref "C14") (pin "2") (pinfunction "2_2") (pintype "passive"))
      (node (ref "C15") (pin "2") (pinfunction "2_2") (pintype "passive"))
      (node (ref "C16") (pin "2") (pinfunction "2_2") (pintype "passive"))
      (node (ref "C17") (pin "2") (pinfunction "2_2") (pintype "passive"))
      (node (ref "C2") (pin "2") (pinfunction "2_2") (pintype "passive"))
      (node (ref "C3") (pin "2") (pinfunction "2_2") (pintype "passive"))
      (node (ref "C4") (pin "2") (pinfunction "2_2") (pintype "passive"))
      (node (ref "C5") (pin "2") (pinfunction "2_2") (pintype "passive"))
      (node (ref "C6") (pin "2") (pinfunction "2_2") (pintype "passive"))
      (node (ref "C7") (pin "2") (pinfunction "2_2") (pintype "passive"))
      (node (ref "C8") (pin "2") (pinfunction "2_2") (pintype "passive"))
      (node (ref "C9") (pin "2") (pinfunction "2_2") (pintype "passive"))
      (node (ref "D1") (pin "2") (pinfunction "A_2") (pintype "power_in"))
      (node (ref "J1") (pin "1") (pinfunction "GND_1") (pintype "passive"))
      (node (ref "J2") (pin "4") (pinfunction "GND_4") (pintype "passive"))
      (node (ref "J3") (pin "4") (pinfunction "GND_4") (pintype "passive"))
      (node (ref "J4") (pin "4") (pinfunction "GND_4") (pintype "passive"))
      (node (ref "J5") (pin "4") (pinfunction "GND_4") (pintype "passive"))
      (node (ref "Q1") (pin "2") (pinfunction "S_2") (pintype "bidirectional"))
      (node (ref "Q2") (pin "2") (pinfunction "S_2") (pintype "bidirectional"))
      (node (ref "Q3") (pin "2") (pinfunction "S_2") (pintype "bidirectional"))
      (node (ref "Q4") (pin "2") (pinfunction "S_2") (pintype "bidirectional"))
      (node (ref "R16") (pin "1") (pinfunction "1_1") (pintype "passive"))
      (node (ref "R9") (pin "1") (pinfunction "1_1") (pintype "passive"))
      (node (ref "S1") (pin "1") (pinfunction "O_1") (pintype "passive"))
      (node (ref "TP1") (pin "1") (pinfunction "P$1_1") (pintype "bidirectional"))
      (node (ref "U1") (pin "7") (pinfunction "GND_7") (pintype "power_in"))
      (node (ref "U10") (pin "8") (pinfunction "GND_8") (pintype "power_in"))
      (node (ref "U10") (pin "EP") (pinfunction "GND_EP") (pintype "power_in"))
      (node (ref "U11") (pin "2") (pinfunction "GND_2") (pintype "power_in"))
      (node (ref "U12") (pin "2") (pinfunction "VSS_2") (pintype "passive"))
      (node (ref "U12") (pin "6") (pinfunction "VIN-_6") (pintype "input"))
      (node (ref "U13") (pin "4") (pinfunction "GND_4") (pintype "power_in"))
      (node (ref "U14") (pin "2") (pinfunction "GND_2") (pintype "power_in"))
      (node (ref "U14") (pin "EP") (pinfunction "GND_EP") (pintype "power_in"))
      (node (ref "U15") (pin "2") (pinfunction "GND_2") (pintype "power_in"))
      (node (ref "U15") (pin "EP") (pinfunction "GND_EP") (pintype "power_in"))
      (node (ref "U16") (pin "2") (pinfunction "GND_2") (pintype "power_in"))
      (node (ref "U16") (pin "EP") (pinfunction "GND_EP") (pintype "power_in"))
      (node (ref "U17") (pin "2") (pinfunction "GND_2") (pintype "power_in"))
      (node (ref "U17") (pin "EP") (pinfunction "GND_EP") (pintype "power_in"))
      (node (ref "U18") (pin "3") (pinfunction "GND_3") (pintype "power_in"))
      (node (ref "U19") (pin "3") (pinfunction "GND_3") (pintype "power_in"))
      (node (ref "U2") (pin "8") (pinfunction "GND_8") (pintype "power_in"))
      (node (ref "U20") (pin "3") (pinfunction "GND_3") (pintype "power_in"))
      (node (ref "U21") (pin "3") (pinfunction "GND_3") (pintype "power_in"))
      (node (ref "U22") (pin "3") (pinfunction "GND_3") (pintype "power_in"))
      (node (ref "U3") (pin "2") (pinfunction "GND_2") (pintype "power_in"))
      (node (ref "U3") (pin "EP") (pinfunction "GND_EP") (pintype "power_in"))
      (node (ref "U4") (pin "11") (pinfunction "GND_11") (pintype "power_in"))
      (node (ref "U5") (pin "11") (pinfunction "GND_11") (pintype "power_in"))
      (node (ref "U6") (pin "7") (pinfunction "GND_7") (pintype "power_in"))
      (node (ref "U7") (pin "2") (pinfunction "GND_2") (pintype "power_in"))
      (node (ref "U7") (pin "5") (pinfunction "WP_5") (pintype "input"))
      (node (ref "U8") (pin "18") (pinfunction "A0_18") (pintype "input"))
      (node (ref "U8") (pin "24") (pinfunction "A2_24") (pintype "input"))
      (node (ref "U8") (pin "9") (pinfunction "VSS_9") (pintype "power_in"))
      (node (ref "U8") (pin "EP") (pinfunction "VSS_EP") (pintype "power_in"))
      (node (ref "U9") (pin "4") (pinfunction "GND_4") (pintype "power_in"))
      (node (ref "U9") (pin "EP") (pinfunction "GND_EP") (pintype "power_in"))
    )
    (net (code "24") (name "I2C_OB_EN") (class "Default")
      (node (ref "J1") (pin "6") (pinfunction "RX_6") (pintype "passive"))
      (node (ref "R12") (pin "1") (pinfunction "1_1") (pintype "passive"))
      (node (ref "U1") (pin "11") (pinfunction "A5_11") (pintype "input"))
      (node (ref "U22") (pin "2") (pinfunction "B_2") (pintype "input"))
    )
    (net (code "25") (name "INTB") (class "Default")
      (node (ref "J1") (pin "5") (pinfunction "TX_5") (pintype "passive"))
      (node (ref "R13") (pin "1") (pinfunction "1_1") (pintype "passive"))
      (node (ref "TP6") (pin "1") (pinfunction "P$1_1") (pintype "bidirectional"))
      (node (ref "U8") (pin "22") (pinfunction "~{INT}_22") (pintype "output"))
    )
    (net (code "26") (name "LATCH1") (class "Default")
      (node (ref "U2") (pin "7") (pinfunction "S2_7") (pintype "input"))
      (node (ref "U5") (pin "1") (pinfunction "OUTA_1") (pintype "output"))
    )
    (net (code "27") (name "LATCH2") (class "Default")
      (node (ref "U2") (pin "3") (pinfunction "S1_3") (pintype "input"))
      (node (ref "U5") (pin "7") (pinfunction "OUTB_7") (pintype "output"))
    )
    (net (code "28") (name "LATCH3") (class "Default")
      (node (ref "U2") (pin "11") (pinfunction "S3_11") (pintype "input"))
      (node (ref "U5") (pin "8") (pinfunction "OUTC_8") (pintype "output"))
    )
    (net (code "29") (name "LATCH4") (class "Default")
      (node (ref "U2") (pin "15") (pinfunction "S4_15") (pintype "input"))
      (node (ref "U5") (pin "14") (pinfunction "OUTD_14") (pintype "output"))
    )
    (net (code "30") (name "LOOPBACK_EN") (class "Default")
      (node (ref "U22") (pin "1") (pinfunction "A_1") (pintype "input"))
      (node (ref "U8") (pin "16") (pinfunction "P1_6_16") (pintype "bidirectional"))
    )
    (net (code "31") (name "MOS_CTRL1") (class "Default")
      (node (ref "Q1") (pin "1") (pinfunction "G_1") (pintype "bidirectional"))
      (node (ref "U6") (pin "11") (pinfunction "Y4_11") (pintype "output"))
    )
    (net (code "32") (name "MOS_CTRL2") (class "Default")
      (node (ref "Q2") (pin "1") (pinfunction "G_1") (pintype "bidirectional"))
      (node (ref "U6") (pin "3") (pinfunction "Y1_3") (pintype "output"))
    )
    (net (code "33") (name "MOS_CTRL3") (class "Default")
      (node (ref "Q3") (pin "1") (pinfunction "G_1") (pintype "bidirectional"))
      (node (ref "U6") (pin "8") (pinfunction "Y3_8") (pintype "output"))
    )
    (net (code "34") (name "MOS_CTRL4") (class "Default")
      (node (ref "Q4") (pin "1") (pinfunction "G_1") (pintype "bidirectional"))
      (node (ref "U6") (pin "6") (pinfunction "Y2_6") (pintype "output"))
    )
    (net (code "35") (name "MUX_EN") (class "Default")
      (node (ref "U10") (pin "6") (pinfunction "~{E}_6") (pintype "input"))
      (node (ref "U9") (pin "5") (pinfunction "P3_5") (pintype "bidirectional"))
    )
    (net (code "36") (name "MUX_SEL0") (class "Default")
      (node (ref "U10") (pin "10") (pinfunction "S0_10") (pintype "input"))
      (node (ref "U9") (pin "1") (pinfunction "P0_1") (pintype "bidirectional"))
    )
    (net (code "37") (name "MUX_SEL1") (class "Default")
      (node (ref "U10") (pin "9") (pinfunction "S1_9") (pintype "input"))
      (node (ref "U9") (pin "2") (pinfunction "P1_2") (pintype "bidirectional"))
    )
    (net (code "38") (name "MUX_SEL2") (class "Default")
      (node (ref "U11") (pin "6") (pinfunction "S_6") (pintype "input"))
      (node (ref "U9") (pin "3") (pinfunction "P2_3") (pintype "bidirectional"))
    )
    (net (code "39") (name "Net-(Q1-D)") (class "Default")
      (node (ref "Q1") (pin "3") (pinfunction "D_3") (pintype "bidirectional"))
      (node (ref "Q5") (pin "1") (pinfunction "G_1") (pintype "bidirectional"))
      (node (ref "R1") (pin "1") (pinfunction "1_1") (pintype "passive"))
    )
    (net (code "40") (name "Net-(Q2-D)") (class "Default")
      (node (ref "Q2") (pin "3") (pinfunction "D_3") (pintype "bidirectional"))
      (node (ref "Q6") (pin "1") (pinfunction "G_1") (pintype "bidirectional"))
      (node (ref "R2") (pin "1") (pinfunction "1_1") (pintype "passive"))
    )
    (net (code "41") (name "Net-(Q3-D)") (class "Default")
      (node (ref "Q3") (pin "3") (pinfunction "D_3") (pintype "bidirectional"))
      (node (ref "Q7") (pin "1") (pinfunction "G_1") (pintype "bidirectional"))
      (node (ref "R3") (pin "1") (pinfunction "1_1") (pintype "passive"))
    )
    (net (code "42") (name "Net-(Q4-D)") (class "Default")
      (node (ref "Q4") (pin "3") (pinfunction "D_3") (pintype "bidirectional"))
      (node (ref "Q8") (pin "1") (pinfunction "G_1") (pintype "bidirectional"))
      (node (ref "R4") (pin "1") (pinfunction "1_1") (pintype "passive"))
    )
    (net (code "43") (name "Net-(U10-1Z)") (class "Default")
      (node (ref "U10") (pin "13") (pinfunction "1Z_13") (pintype "output"))
      (node (ref "U11") (pin "1") (pinfunction "B2_1") (pintype "bidirectional"))
    )
    (net (code "44") (name "Net-(U10-2Z)") (class "Default")
      (node (ref "R15") (pin "2") (pinfunction "2_2") (pintype "passive"))
      (node (ref "U10") (pin "3") (pinfunction "2Z_3") (pintype "output"))
    )
    (net (code "45") (name "Net-(U11-B1)") (class "Default")
      (node (ref "R15") (pin "1") (pinfunction "1_1") (pintype "passive"))
      (node (ref "R16") (pin "2") (pinfunction "2_2") (pintype "passive"))
      (node (ref "U11") (pin "3") (pinfunction "B1_3") (pintype "bidirectional"))
    )
    (net (code "46") (name "Net-(U13-EN)") (class "Default")
      (node (ref "U13") (pin "5") (pinfunction "EN_5") (pintype "input"))
      (node (ref "U22") (pin "4") (pinfunction "Y_4") (pintype "output"))
    )
    (net (code "47") (name "PORT1_SCL") (class "Default")
      (node (ref "J2") (pin "3") (pinfunction "SCL_3") (pintype "passive"))
      (node (ref "R23") (pin "1") (pinfunction "1_1") (pintype "passive"))
      (node (ref "U14") (pin "5") (pinfunction "SCL_B_5") (pintype "open_collector"))
    )
    (net (code "48") (name "PORT1_SDA") (class "Default")
      (node (ref "J2") (pin "1") (pinfunction "SDA_1") (pintype "passive"))
      (node (ref "R19") (pin "1") (pinfunction "1_1") (pintype "passive"))
      (node (ref "U14") (pin "4") (pinfunction "SDA_B_4") (pintype "open_collector"))
    )
    (net (code "49") (name "PORT2_SCL") (class "Default")
      (node (ref "J3") (pin "3") (pinfunction "SCL_3") (pintype "passive"))
      (node (ref "R24") (pin "1") (pinfunction "1_1") (pintype "passive"))
      (node (ref "U15") (pin "5") (pinfunction "SCL_B_5") (pintype "open_collector"))
    )
    (net (code "50") (name "PORT2_SDA") (class "Default")
      (node (ref "J3") (pin "1") (pinfunction "SDA_1") (pintype "passive"))
      (node (ref "R20") (pin "1") (pinfunction "1_1") (pintype "passive"))
      (node (ref "U15") (pin "4") (pinfunction "SDA_B_4") (pintype "open_collector"))
    )
    (net (code "51") (name "PORT3_SCL") (class "Default")
      (node (ref "J4") (pin "3") (pinfunction "SCL_3") (pintype "passive"))
      (node (ref "R25") (pin "1") (pinfunction "1_1") (pintype "passive"))
      (node (ref "U16") (pin "5") (pinfunction "SCL_B_5") (pintype "open_collector"))
    )
    (net (code "52") (name "PORT3_SDA") (class "Default")
      (node (ref "J4") (pin "1") (pinfunction "SDA_1") (pintype "passive"))
      (node (ref "R21") (pin "1") (pinfunction "1_1") (pintype "passive"))
      (node (ref "U16") (pin "4") (pinfunction "SDA_B_4") (pintype "open_collector"))
    )
    (net (code "53") (name "PORT4_SCL") (class "Default")
      (node (ref "J5") (pin "3") (pinfunction "SCL_3") (pintype "passive"))
      (node (ref "R26") (pin "1") (pinfunction "1_1") (pintype "passive"))
      (node (ref "U17") (pin "5") (pinfunction "SCL_B_5") (pintype "open_collector"))
    )
    (net (code "54") (name "PORT4_SDA") (class "Default")
      (node (ref "J5") (pin "1") (pinfunction "SDA_1") (pintype "passive"))
      (node (ref "R22") (pin "1") (pinfunction "1_1") (pintype "passive"))
      (node (ref "U17") (pin "4") (pinfunction "SDA_B_4") (pintype "open_collector"))
    )
    (net (code "55") (name "POS_DETECT") (class "Default")
      (node (ref "R11") (pin "1") (pinfunction "1_1") (pintype "passive"))
      (node (ref "S1") (pin "2") (pinfunction "P_2") (pintype "passive"))
      (node (ref "U8") (pin "14") (pinfunction "P1_4_14") (pintype "bidirectional"))
    )
    (net (code "56") (name "SCL") (class "Default")
      (node (ref "J1") (pin "4") (pinfunction "SCL_4") (pintype "passive"))
      (node (ref "R18") (pin "1") (pinfunction "1_1") (pintype "passive"))
      (node (ref "TP3") (pin "1") (pinfunction "P$1_1") (pintype "bidirectional"))
      (node (ref "U13") (pin "3") (pinfunction "A2_3") (pintype "bidirectional"))
      (node (ref "U14") (pin "8") (pinfunction "SCL_A_8") (pintype "open_collector"))
      (node (ref "U15") (pin "8") (pinfunction "SCL_A_8") (pintype "open_collector"))
      (node (ref "U16") (pin "8") (pinfunction "SCL_A_8") (pintype "open_collector"))
      (node (ref "U17") (pin "8") (pinfunction "SCL_A_8") (pintype "open_collector"))
    )
    (net (code "57") (name "SCL_OB") (class "Default")
      (node (ref "TP5") (pin "1") (pinfunction "P$1_1") (pintype "bidirectional"))
      (node (ref "U12") (pin "3") (pinfunction "SCL_3") (pintype "bidirectional"))
      (node (ref "U13") (pin "6") (pinfunction "B2_6") (pintype "bidirectional"))
      (node (ref "U7") (pin "1") (pinfunction "SCL_1") (pintype "input"))
      (node (ref "U8") (pin "19") (pinfunction "SCL_19") (pintype "input"))
      (node (ref "U9") (pin "6") (pinfunction "SCL_6") (pintype "input"))
    )
    (net (code "58") (name "SDA") (class "Default")
      (node (ref "J1") (pin "3") (pinfunction "SDA_3") (pintype "passive"))
      (node (ref "R17") (pin "1") (pinfunction "1_1") (pintype "passive"))
      (node (ref "TP2") (pin "1") (pinfunction "P$1_1") (pintype "bidirectional"))
      (node (ref "U13") (pin "2") (pinfunction "A1_2") (pintype "bidirectional"))
      (node (ref "U14") (pin "1") (pinfunction "SDA_A_1") (pintype "open_collector"))
      (node (ref "U15") (pin "1") (pinfunction "SDA_A_1") (pintype "open_collector"))
      (node (ref "U16") (pin "1") (pinfunction "SDA_A_1") (pintype "open_collector"))
      (node (ref "U17") (pin "1") (pinfunction "SDA_A_1") (pintype "open_collector"))
    )
    (net (code "59") (name "SDA_OB") (class "Default")
      (node (ref "TP4") (pin "1") (pinfunction "P$1_1") (pintype "bidirectional"))
      (node (ref "U12") (pin "4") (pinfunction "SDA_4") (pintype "bidirectional"))
      (node (ref "U13") (pin "7") (pinfunction "B1_7") (pintype "bidirectional"))
      (node (ref "U7") (pin "3") (pinfunction "SDA_3") (pintype "bidirectional"))
      (node (ref "U8") (pin "20") (pinfunction "SDA_20") (pintype "bidirectional"))
      (node (ref "U9") (pin "7") (pinfunction "SDA_7") (pintype "bidirectional"))
    )
    (net (code "60") (name "SENSE1") (class "Default")
      (node (ref "R31") (pin "1") (pinfunction "1_1") (pintype "passive"))
      (node (ref "U10") (pin "12") (pinfunction "1Y0_12") (pintype "input"))
      (node (ref "U4") (pin "7") (pinfunction "OUT2_7") (pintype "output"))
    )
    (net (code "61") (name "SENSE1+") (class "Default")
      (node (ref "Q5") (pin "3") (pinfunction "D_3") (pintype "bidirectional"))
      (node (ref "R5") (pin "1") (pinfunction "1_1") (pintype "passive"))
      (node (ref "U4") (pin "5") (pinfunction "IN2+_5") (pintype "input"))
    )
    (net (code "62") (name "SENSE1_FILT") (class "Default")
      (node (ref "C14") (pin "1") (pinfunction "1_1") (pintype "passive"))
      (node (ref "R31") (pin "2") (pinfunction "2_2") (pintype "passive"))
      (node (ref "U5") (pin "2") (pinfunction "INA-_2") (pintype "input"))
    )
    (net (code "63") (name "SENSE2") (class "Default")
      (node (ref "R32") (pin "1") (pinfunction "1_1") (pintype "passive"))
      (node (ref "U10") (pin "14") (pinfunction "1Y1_14") (pintype "input"))
      (node (ref "U4") (pin "1") (pinfunction "OUT1_1") (pintype "output"))
    )
    (net (code "64") (name "SENSE2+") (class "Default")
      (node (ref "Q6") (pin "3") (pinfunction "D_3") (pintype "bidirectional"))
      (node (ref "R6") (pin "1") (pinfunction "1_1") (pintype "passive"))
      (node (ref "U4") (pin "3") (pinfunction "IN1+_3") (pintype "input"))
    )
    (net (code "65") (name "SENSE2_FILT") (class "Default")
      (node (ref "C15") (pin "1") (pinfunction "1_1") (pintype "passive"))
      (node (ref "R32") (pin "2") (pinfunction "2_2") (pintype "passive"))
      (node (ref "U5") (pin "6") (pinfunction "INB-_6") (pintype "input"))
    )
    (net (code "66") (name "SENSE3") (class "Default")
      (node (ref "R33") (pin "1") (pinfunction "1_1") (pintype "passive"))
      (node (ref "U10") (pin "15") (pinfunction "1Y2_15") (pintype "input"))
      (node (ref "U4") (pin "14") (pinfunction "OUT4_14") (pintype "output"))
    )
    (net (code "67") (name "SENSE3+") (class "Default")
      (node (ref "Q7") (pin "3") (pinfunction "D_3") (pintype "bidirectional"))
      (node (ref "R7") (pin "1") (pinfunction "1_1") (pintype "passive"))
      (node (ref "U4") (pin "12") (pinfunction "IN4+_12") (pintype "input"))
    )
    (net (code "68") (name "SENSE3_FILT") (class "Default")
      (node (ref "C16") (pin "1") (pinfunction "1_1") (pintype "passive"))
      (node (ref "R33") (pin "2") (pinfunction "2_2") (pintype "passive"))
      (node (ref "U5") (pin "9") (pinfunction "INC-_9") (pintype "input"))
    )
    (net (code "69") (name "SENSE4") (class "Default")
      (node (ref "R34") (pin "1") (pinfunction "1_1") (pintype "passive"))
      (node (ref "U10") (pin "11") (pinfunction "1Y3_11") (pintype "input"))
      (node (ref "U4") (pin "8") (pinfunction "OUT3_8") (pintype "output"))
    )
    (net (code "70") (name "SENSE4+") (class "Default")
      (node (ref "Q8") (pin "3") (pinfunction "D_3") (pintype "bidirectional"))
      (node (ref "R8") (pin "1") (pinfunction "1_1") (pintype "passive"))
      (node (ref "U4") (pin "10") (pinfunction "IN3+_10") (pintype "input"))
    )
    (net (code "71") (name "SENSE4_FILT") (class "Default")
      (node (ref "C17") (pin "1") (pinfunction "1_1") (pintype "passive"))
      (node (ref "R34") (pin "2") (pinfunction "2_2") (pintype "passive"))
      (node (ref "U5") (pin "13") (pinfunction "IND-_13") (pintype "input"))
    )
    (net (code "72") (name "SENSE_EN") (class "Default")
      (node (ref "R9") (pin "2") (pinfunction "2_2") (pintype "passive"))
      (node (ref "U2") (pin "5") (pinfunction "EN_5") (pintype "input"))
      (node (ref "U3") (pin "4") (pinfunction "EN_4") (pintype "input"))
      (node (ref "U8") (pin "15") (pinfunction "P1_5_15") (pintype "bidirectional"))
    )
    (net (code "73") (name "SWITCHED_SENSE") (class "Default")
      (node (ref "U11") (pin "4") (pinfunction "A_4") (pintype "bidirectional"))
      (node (ref "U12") (pin "1") (pinfunction "VIN+_1") (pintype "input"))
    )
    (net (code "74") (name "VPORT1_OUT") (class "Default")
      (node (ref "C13") (pin "1") (pinfunction "1_1") (pintype "passive"))
      (node (ref "J2") (pin "2") (pinfunction "3V3_2") (pintype "passive"))
      (node (ref "R19") (pin "2") (pinfunction "2_2") (pintype "passive"))
      (node (ref "R23") (pin "2") (pinfunction "2_2") (pintype "passive"))
      (node (ref "R5") (pin "2") (pinfunction "2_2") (pintype "passive"))
      (node (ref "U10") (pin "1") (pinfunction "2Y0_1") (pintype "input"))
      (node (ref "U14") (pin "6") (pinfunction "VCCB_6") (pintype "power_in"))
      (node (ref "U4") (pin "6") (pinfunction "IN2-_6") (pintype "input"))
    )
    (net (code "75") (name "VPORT2_OUT") (class "Default")
      (node (ref "C10") (pin "1") (pinfunction "1_1") (pintype "passive"))
      (node (ref "J3") (pin "2") (pinfunction "3V3_2") (pintype "passive"))
      (node (ref "R20") (pin "2") (pinfunction "2_2") (pintype "passive"))
      (node (ref "R24") (pin "2") (pinfunction "2_2") (pintype "passive"))
      (node (ref "R6") (pin "2") (pinfunction "2_2") (pintype "passive"))
      (node (ref "U10") (pin "5") (pinfunction "2Y1_5") (pintype "input"))
      (node (ref "U15") (pin "6") (pinfunction "VCCB_6") (pintype "power_in"))
      (node (ref "U4") (pin "2") (pinfunction "IN1-_2") (pintype "input"))
    )
    (net (code "76") (name "VPORT3_OUT") (class "Default")
      (node (ref "C11") (pin "1") (pinfunction "1_1") (pintype "passive"))
      (node (ref "J4") (pin "2") (pinfunction "3V3_2") (pintype "passive"))
      (node (ref "R21") (pin "2") (pinfunction "2_2") (pintype "passive"))
      (node (ref "R25") (pin "2") (pinfunction "2_2") (pintype "passive"))
      (node (ref "R7") (pin "2") (pinfunction "2_2") (pintype "passive"))
      (node (ref "U10") (pin "2") (pinfunction "2Y2_2") (pintype "input"))
      (node (ref "U16") (pin "6") (pinfunction "VCCB_6") (pintype "power_in"))
      (node (ref "U4") (pin "13") (pinfunction "IN4-_13") (pintype "input"))
    )
    (net (code "77") (name "VPORT4_OUT") (class "Default")
      (node (ref "C12") (pin "1") (pinfunction "1_1") (pintype "passive"))
      (node (ref "J5") (pin "2") (pinfunction "3V3_2") (pintype "passive"))
      (node (ref "R22") (pin "2") (pinfunction "2_2") (pintype "passive"))
      (node (ref "R26") (pin "2") (pinfunction "2_2") (pintype "passive"))
      (node (ref "R8") (pin "2") (pinfunction "2_2") (pintype "passive"))
      (node (ref "U10") (pin "4") (pinfunction "2Y3_4") (pintype "input"))
      (node (ref "U17") (pin "6") (pinfunction "VCCB_6") (pintype "power_in"))
      (node (ref "U4") (pin "9") (pinfunction "IN3-_9") (pintype "input"))
    )
    (net (code "78") (name "VREF") (class "Default")
      (node (ref "D1") (pin "1") (pinfunction "C_1") (pintype "power_in"))
      (node (ref "R10") (pin "1") (pinfunction "1_1") (pintype "passive"))
      (node (ref "U5") (pin "10") (pinfunction "INC+_10") (pintype "input"))
      (node (ref "U5") (pin "12") (pinfunction "IND+_12") (pintype "input"))
      (node (ref "U5") (pin "3") (pinfunction "INA+_3") (pintype "input"))
      (node (ref "U5") (pin "5") (pinfunction "INB+_5") (pintype "input"))
    )
    (net (code "79") (name "unconnected-(U1-Y6-Pad12)") (class "Default")
      (node (ref "U1") (pin "12") (pinfunction "Y6_12") (pintype "output"))
    )
    (net (code "80") (name "unconnected-(U8-P1_7-Pad17)") (class "Default")
      (node (ref "U8") (pin "17") (pinfunction "P1_7_17") (pintype "bidirectional"))
    )
    (net (code "81") (name "~{FAULT1}") (class "Default")
      (node (ref "U1") (pin "8") (pinfunction "Y4_8") (pintype "output"))
      (node (ref "U6") (pin "13") (pinfunction "B4_13") (pintype "input"))
    )
    (net (code "82") (name "~{FAULT2}") (class "Default")
      (node (ref "U1") (pin "4") (pinfunction "Y2_4") (pintype "output"))
      (node (ref "U6") (pin "2") (pinfunction "B1_2") (pintype "input"))
    )
    (net (code "83") (name "~{FAULT3}") (class "Default")
      (node (ref "U1") (pin "6") (pinfunction "Y3_6") (pintype "output"))
      (node (ref "U6") (pin "10") (pinfunction "B3_10") (pintype "input"))
    )
    (net (code "84") (name "~{FAULT4}") (class "Default")
      (node (ref "U1") (pin "2") (pinfunction "Y1_2") (pintype "output"))
      (node (ref "U6") (pin "5") (pinfunction "B2_5") (pintype "input"))
    )
    (net (code "85") (name "~{I2C_OB_EN}") (class "Default")
      (node (ref "U1") (pin "10") (pinfunction "Y5_10") (pintype "output"))
      (node (ref "U18") (pin "1") (pinfunction "A_1") (pintype "input"))
      (node (ref "U19") (pin "1") (pinfunction "A_1") (pintype "input"))
      (node (ref "U20") (pin "1") (pinfunction "A_1") (pintype "input"))
      (node (ref "U21") (pin "1") (pinfunction "A_1") (pintype "input"))
    )
  )
)
